# hdb44_passthrough.net
KiCad netlist of a schematic drawn in Altium Designer
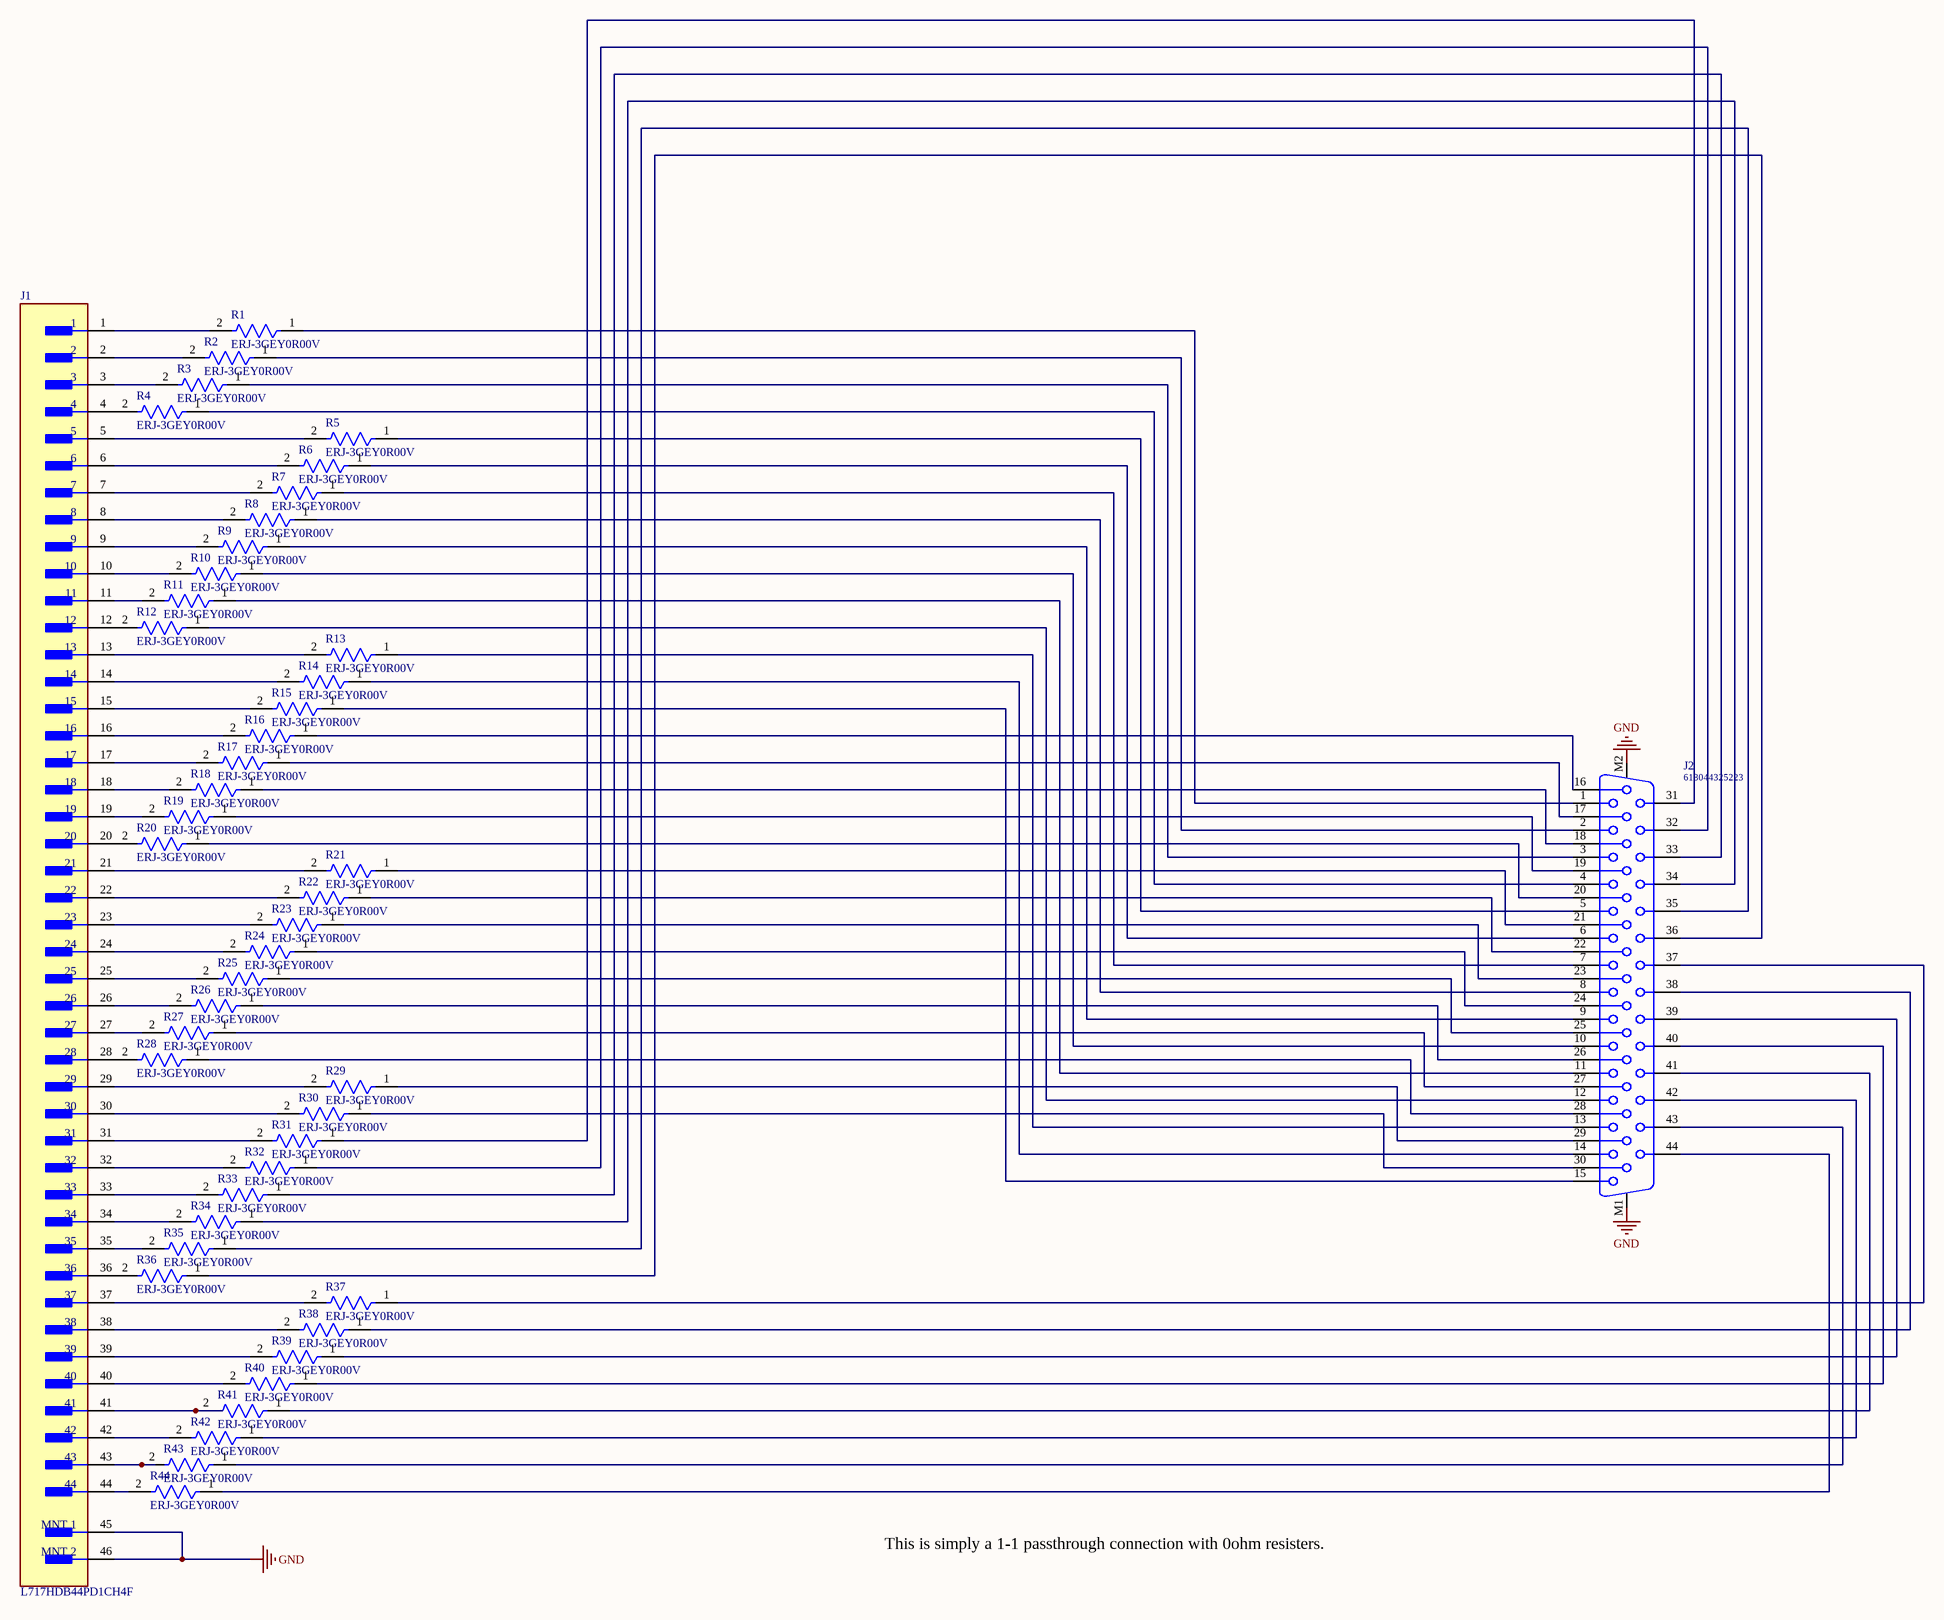
[diagram p0: hdb44_passthrough.SchDoc]

(export (version "E")
  (design (tool "Eeschema 10.0.6"))
  (components
    (comp (ref "J1")
      (value "L717HDB44PD1CH4F")
      (footprint "FP-L717HDB44PD1CH4F-MFG")
      (description "CONN DSUB HD PLUG 44POS R/A SLDR")
      (libsource (lib "Altium Content Vault") (part "41ccbbee039f7fbc4919d80e2a23f43"))
    )
    (comp (ref "J2")
      (value "618044325223")
      (footprint "618044325223")
      (description "Female High Density PCB Connector without Hex Screw WR-DSUB, Angled, 44 pins")
      (fields (field (name "MANUFACTURER") "Wurth Elektronik") (field (name "PUBLISHER") "WurthElektronik"))
      (libsource (lib "Altium Content Vault") (part "WE-CN-3S-2F-D44"))
    )
    (comp (ref "R1")
      (value "ERJ-3GEY0R00V")
      (footprint "FP-ERJ-3GEY0R00V-MFG")
      (description "RES SMD 0 OHM JUMPER 1/10W 0603")
      (fields (field (name "TOLERANCE") "5%") (field (name "MANUFACTURER") "Panasonic"))
      (libsource (lib "Altium Content Vault") (part "1029c3af85768c4190bb7ad29bc67b5"))
    )
    (comp (ref "R2")
      (value "ERJ-3GEY0R00V")
      (footprint "FP-ERJ-3GEY0R00V-MFG")
      (description "RES SMD 0 OHM JUMPER 1/10W 0603")
      (fields (field (name "TOLERANCE") "5%") (field (name "MANUFACTURER") "Panasonic"))
      (libsource (lib "Altium Content Vault") (part "1029c3af85768c4190bb7ad29bc67b5"))
    )
    (comp (ref "R3")
      (value "ERJ-3GEY0R00V")
      (footprint "FP-ERJ-3GEY0R00V-MFG")
      (description "RES SMD 0 OHM JUMPER 1/10W 0603")
      (fields (field (name "TOLERANCE") "5%") (field (name "MANUFACTURER") "Panasonic"))
      (libsource (lib "Altium Content Vault") (part "1029c3af85768c4190bb7ad29bc67b5"))
    )
    (comp (ref "R4")
      (value "ERJ-3GEY0R00V")
      (footprint "FP-ERJ-3GEY0R00V-MFG")
      (description "RES SMD 0 OHM JUMPER 1/10W 0603")
      (fields (field (name "TOLERANCE") "5%") (field (name "MANUFACTURER") "Panasonic"))
      (libsource (lib "Altium Content Vault") (part "1029c3af85768c4190bb7ad29bc67b5"))
    )
    (comp (ref "R5")
      (value "ERJ-3GEY0R00V")
      (footprint "FP-ERJ-3GEY0R00V-MFG")
      (description "RES SMD 0 OHM JUMPER 1/10W 0603")
      (fields (field (name "TOLERANCE") "5%") (field (name "MANUFACTURER") "Panasonic"))
      (libsource (lib "Altium Content Vault") (part "1029c3af85768c4190bb7ad29bc67b5"))
    )
    (comp (ref "R6")
      (value "ERJ-3GEY0R00V")
      (footprint "FP-ERJ-3GEY0R00V-MFG")
      (description "RES SMD 0 OHM JUMPER 1/10W 0603")
      (fields (field (name "TOLERANCE") "5%") (field (name "MANUFACTURER") "Panasonic"))
      (libsource (lib "Altium Content Vault") (part "1029c3af85768c4190bb7ad29bc67b5"))
    )
    (comp (ref "R7")
      (value "ERJ-3GEY0R00V")
      (footprint "FP-ERJ-3GEY0R00V-MFG")
      (description "RES SMD 0 OHM JUMPER 1/10W 0603")
      (fields (field (name "TOLERANCE") "5%") (field (name "MANUFACTURER") "Panasonic"))
      (libsource (lib "Altium Content Vault") (part "1029c3af85768c4190bb7ad29bc67b5"))
    )
    (comp (ref "R8")
      (value "ERJ-3GEY0R00V")
      (footprint "FP-ERJ-3GEY0R00V-MFG")
      (description "RES SMD 0 OHM JUMPER 1/10W 0603")
      (fields (field (name "TOLERANCE") "5%") (field (name "MANUFACTURER") "Panasonic"))
      (libsource (lib "Altium Content Vault") (part "1029c3af85768c4190bb7ad29bc67b5"))
    )
    (comp (ref "R9")
      (value "ERJ-3GEY0R00V")
      (footprint "FP-ERJ-3GEY0R00V-MFG")
      (description "RES SMD 0 OHM JUMPER 1/10W 0603")
      (fields (field (name "TOLERANCE") "5%") (field (name "MANUFACTURER") "Panasonic"))
      (libsource (lib "Altium Content Vault") (part "1029c3af85768c4190bb7ad29bc67b5"))
    )
    (comp (ref "R10")
      (value "ERJ-3GEY0R00V")
      (footprint "FP-ERJ-3GEY0R00V-MFG")
      (description "RES SMD 0 OHM JUMPER 1/10W 0603")
      (fields (field (name "TOLERANCE") "5%") (field (name "MANUFACTURER") "Panasonic"))
      (libsource (lib "Altium Content Vault") (part "1029c3af85768c4190bb7ad29bc67b5"))
    )
    (comp (ref "R11")
      (value "ERJ-3GEY0R00V")
      (footprint "FP-ERJ-3GEY0R00V-MFG")
      (description "RES SMD 0 OHM JUMPER 1/10W 0603")
      (fields (field (name "TOLERANCE") "5%") (field (name "MANUFACTURER") "Panasonic"))
      (libsource (lib "Altium Content Vault") (part "1029c3af85768c4190bb7ad29bc67b5"))
    )
    (comp (ref "R12")
      (value "ERJ-3GEY0R00V")
      (footprint "FP-ERJ-3GEY0R00V-MFG")
      (description "RES SMD 0 OHM JUMPER 1/10W 0603")
      (fields (field (name "TOLERANCE") "5%") (field (name "MANUFACTURER") "Panasonic"))
      (libsource (lib "Altium Content Vault") (part "1029c3af85768c4190bb7ad29bc67b5"))
    )
    (comp (ref "R13")
      (value "ERJ-3GEY0R00V")
      (footprint "FP-ERJ-3GEY0R00V-MFG")
      (description "RES SMD 0 OHM JUMPER 1/10W 0603")
      (fields (field (name "TOLERANCE") "5%") (field (name "MANUFACTURER") "Panasonic"))
      (libsource (lib "Altium Content Vault") (part "1029c3af85768c4190bb7ad29bc67b5"))
    )
    (comp (ref "R14")
      (value "ERJ-3GEY0R00V")
      (footprint "FP-ERJ-3GEY0R00V-MFG")
      (description "RES SMD 0 OHM JUMPER 1/10W 0603")
      (fields (field (name "TOLERANCE") "5%") (field (name "MANUFACTURER") "Panasonic"))
      (libsource (lib "Altium Content Vault") (part "1029c3af85768c4190bb7ad29bc67b5"))
    )
    (comp (ref "R15")
      (value "ERJ-3GEY0R00V")
      (footprint "FP-ERJ-3GEY0R00V-MFG")
      (description "RES SMD 0 OHM JUMPER 1/10W 0603")
      (fields (field (name "TOLERANCE") "5%") (field (name "MANUFACTURER") "Panasonic"))
      (libsource (lib "Altium Content Vault") (part "1029c3af85768c4190bb7ad29bc67b5"))
    )
    (comp (ref "R16")
      (value "ERJ-3GEY0R00V")
      (footprint "FP-ERJ-3GEY0R00V-MFG")
      (description "RES SMD 0 OHM JUMPER 1/10W 0603")
      (fields (field (name "TOLERANCE") "5%") (field (name "MANUFACTURER") "Panasonic"))
      (libsource (lib "Altium Content Vault") (part "1029c3af85768c4190bb7ad29bc67b5"))
    )
    (comp (ref "R17")
      (value "ERJ-3GEY0R00V")
      (footprint "FP-ERJ-3GEY0R00V-MFG")
      (description "RES SMD 0 OHM JUMPER 1/10W 0603")
      (fields (field (name "TOLERANCE") "5%") (field (name "MANUFACTURER") "Panasonic"))
      (libsource (lib "Altium Content Vault") (part "1029c3af85768c4190bb7ad29bc67b5"))
    )
    (comp (ref "R18")
      (value "ERJ-3GEY0R00V")
      (footprint "FP-ERJ-3GEY0R00V-MFG")
      (description "RES SMD 0 OHM JUMPER 1/10W 0603")
      (fields (field (name "TOLERANCE") "5%") (field (name "MANUFACTURER") "Panasonic"))
      (libsource (lib "Altium Content Vault") (part "1029c3af85768c4190bb7ad29bc67b5"))
    )
    (comp (ref "R19")
      (value "ERJ-3GEY0R00V")
      (footprint "FP-ERJ-3GEY0R00V-MFG")
      (description "RES SMD 0 OHM JUMPER 1/10W 0603")
      (fields (field (name "TOLERANCE") "5%") (field (name "MANUFACTURER") "Panasonic"))
      (libsource (lib "Altium Content Vault") (part "1029c3af85768c4190bb7ad29bc67b5"))
    )
    (comp (ref "R20")
      (value "ERJ-3GEY0R00V")
      (footprint "FP-ERJ-3GEY0R00V-MFG")
      (description "RES SMD 0 OHM JUMPER 1/10W 0603")
      (fields (field (name "TOLERANCE") "5%") (field (name "MANUFACTURER") "Panasonic"))
      (libsource (lib "Altium Content Vault") (part "1029c3af85768c4190bb7ad29bc67b5"))
    )
    (comp (ref "R21")
      (value "ERJ-3GEY0R00V")
      (footprint "FP-ERJ-3GEY0R00V-MFG")
      (description "RES SMD 0 OHM JUMPER 1/10W 0603")
      (fields (field (name "TOLERANCE") "5%") (field (name "MANUFACTURER") "Panasonic"))
      (libsource (lib "Altium Content Vault") (part "1029c3af85768c4190bb7ad29bc67b5"))
    )
    (comp (ref "R22")
      (value "ERJ-3GEY0R00V")
      (footprint "FP-ERJ-3GEY0R00V-MFG")
      (description "RES SMD 0 OHM JUMPER 1/10W 0603")
      (fields (field (name "TOLERANCE") "5%") (field (name "MANUFACTURER") "Panasonic"))
      (libsource (lib "Altium Content Vault") (part "1029c3af85768c4190bb7ad29bc67b5"))
    )
    (comp (ref "R23")
      (value "ERJ-3GEY0R00V")
      (footprint "FP-ERJ-3GEY0R00V-MFG")
      (description "RES SMD 0 OHM JUMPER 1/10W 0603")
      (fields (field (name "TOLERANCE") "5%") (field (name "MANUFACTURER") "Panasonic"))
      (libsource (lib "Altium Content Vault") (part "1029c3af85768c4190bb7ad29bc67b5"))
    )
    (comp (ref "R24")
      (value "ERJ-3GEY0R00V")
      (footprint "FP-ERJ-3GEY0R00V-MFG")
      (description "RES SMD 0 OHM JUMPER 1/10W 0603")
      (fields (field (name "TOLERANCE") "5%") (field (name "MANUFACTURER") "Panasonic"))
      (libsource (lib "Altium Content Vault") (part "1029c3af85768c4190bb7ad29bc67b5"))
    )
    (comp (ref "R25")
      (value "ERJ-3GEY0R00V")
      (footprint "FP-ERJ-3GEY0R00V-MFG")
      (description "RES SMD 0 OHM JUMPER 1/10W 0603")
      (fields (field (name "TOLERANCE") "5%") (field (name "MANUFACTURER") "Panasonic"))
      (libsource (lib "Altium Content Vault") (part "1029c3af85768c4190bb7ad29bc67b5"))
    )
    (comp (ref "R26")
      (value "ERJ-3GEY0R00V")
      (footprint "FP-ERJ-3GEY0R00V-MFG")
      (description "RES SMD 0 OHM JUMPER 1/10W 0603")
      (fields (field (name "TOLERANCE") "5%") (field (name "MANUFACTURER") "Panasonic"))
      (libsource (lib "Altium Content Vault") (part "1029c3af85768c4190bb7ad29bc67b5"))
    )
    (comp (ref "R27")
      (value "ERJ-3GEY0R00V")
      (footprint "FP-ERJ-3GEY0R00V-MFG")
      (description "RES SMD 0 OHM JUMPER 1/10W 0603")
      (fields (field (name "TOLERANCE") "5%") (field (name "MANUFACTURER") "Panasonic"))
      (libsource (lib "Altium Content Vault") (part "1029c3af85768c4190bb7ad29bc67b5"))
    )
    (comp (ref "R28")
      (value "ERJ-3GEY0R00V")
      (footprint "FP-ERJ-3GEY0R00V-MFG")
      (description "RES SMD 0 OHM JUMPER 1/10W 0603")
      (fields (field (name "TOLERANCE") "5%") (field (name "MANUFACTURER") "Panasonic"))
      (libsource (lib "Altium Content Vault") (part "1029c3af85768c4190bb7ad29bc67b5"))
    )
    (comp (ref "R29")
      (value "ERJ-3GEY0R00V")
      (footprint "FP-ERJ-3GEY0R00V-MFG")
      (description "RES SMD 0 OHM JUMPER 1/10W 0603")
      (fields (field (name "TOLERANCE") "5%") (field (name "MANUFACTURER") "Panasonic"))
      (libsource (lib "Altium Content Vault") (part "1029c3af85768c4190bb7ad29bc67b5"))
    )
    (comp (ref "R30")
      (value "ERJ-3GEY0R00V")
      (footprint "FP-ERJ-3GEY0R00V-MFG")
      (description "RES SMD 0 OHM JUMPER 1/10W 0603")
      (fields (field (name "TOLERANCE") "5%") (field (name "MANUFACTURER") "Panasonic"))
      (libsource (lib "Altium Content Vault") (part "1029c3af85768c4190bb7ad29bc67b5"))
    )
    (comp (ref "R31")
      (value "ERJ-3GEY0R00V")
      (footprint "FP-ERJ-3GEY0R00V-MFG")
      (description "RES SMD 0 OHM JUMPER 1/10W 0603")
      (fields (field (name "TOLERANCE") "5%") (field (name "MANUFACTURER") "Panasonic"))
      (libsource (lib "Altium Content Vault") (part "1029c3af85768c4190bb7ad29bc67b5"))
    )
    (comp (ref "R32")
      (value "ERJ-3GEY0R00V")
      (footprint "FP-ERJ-3GEY0R00V-MFG")
      (description "RES SMD 0 OHM JUMPER 1/10W 0603")
      (fields (field (name "TOLERANCE") "5%") (field (name "MANUFACTURER") "Panasonic"))
      (libsource (lib "Altium Content Vault") (part "1029c3af85768c4190bb7ad29bc67b5"))
    )
    (comp (ref "R33")
      (value "ERJ-3GEY0R00V")
      (footprint "FP-ERJ-3GEY0R00V-MFG")
      (description "RES SMD 0 OHM JUMPER 1/10W 0603")
      (fields (field (name "TOLERANCE") "5%") (field (name "MANUFACTURER") "Panasonic"))
      (libsource (lib "Altium Content Vault") (part "1029c3af85768c4190bb7ad29bc67b5"))
    )
    (comp (ref "R34")
      (value "ERJ-3GEY0R00V")
      (footprint "FP-ERJ-3GEY0R00V-MFG")
      (description "RES SMD 0 OHM JUMPER 1/10W 0603")
      (fields (field (name "TOLERANCE") "5%") (field (name "MANUFACTURER") "Panasonic"))
      (libsource (lib "Altium Content Vault") (part "1029c3af85768c4190bb7ad29bc67b5"))
    )
    (comp (ref "R35")
      (value "ERJ-3GEY0R00V")
      (footprint "FP-ERJ-3GEY0R00V-MFG")
      (description "RES SMD 0 OHM JUMPER 1/10W 0603")
      (fields (field (name "TOLERANCE") "5%") (field (name "MANUFACTURER") "Panasonic"))
      (libsource (lib "Altium Content Vault") (part "1029c3af85768c4190bb7ad29bc67b5"))
    )
    (comp (ref "R36")
      (value "ERJ-3GEY0R00V")
      (footprint "FP-ERJ-3GEY0R00V-MFG")
      (description "RES SMD 0 OHM JUMPER 1/10W 0603")
      (fields (field (name "TOLERANCE") "5%") (field (name "MANUFACTURER") "Panasonic"))
      (libsource (lib "Altium Content Vault") (part "1029c3af85768c4190bb7ad29bc67b5"))
    )
    (comp (ref "R37")
      (value "ERJ-3GEY0R00V")
      (footprint "FP-ERJ-3GEY0R00V-MFG")
      (description "RES SMD 0 OHM JUMPER 1/10W 0603")
      (fields (field (name "TOLERANCE") "5%") (field (name "MANUFACTURER") "Panasonic"))
      (libsource (lib "Altium Content Vault") (part "1029c3af85768c4190bb7ad29bc67b5"))
    )
    (comp (ref "R38")
      (value "ERJ-3GEY0R00V")
      (footprint "FP-ERJ-3GEY0R00V-MFG")
      (description "RES SMD 0 OHM JUMPER 1/10W 0603")
      (fields (field (name "TOLERANCE") "5%") (field (name "MANUFACTURER") "Panasonic"))
      (libsource (lib "Altium Content Vault") (part "1029c3af85768c4190bb7ad29bc67b5"))
    )
    (comp (ref "R39")
      (value "ERJ-3GEY0R00V")
      (footprint "FP-ERJ-3GEY0R00V-MFG")
      (description "RES SMD 0 OHM JUMPER 1/10W 0603")
      (fields (field (name "TOLERANCE") "5%") (field (name "MANUFACTURER") "Panasonic"))
      (libsource (lib "Altium Content Vault") (part "1029c3af85768c4190bb7ad29bc67b5"))
    )
    (comp (ref "R40")
      (value "ERJ-3GEY0R00V")
      (footprint "FP-ERJ-3GEY0R00V-MFG")
      (description "RES SMD 0 OHM JUMPER 1/10W 0603")
      (fields (field (name "TOLERANCE") "5%") (field (name "MANUFACTURER") "Panasonic"))
      (libsource (lib "Altium Content Vault") (part "1029c3af85768c4190bb7ad29bc67b5"))
    )
    (comp (ref "R41")
      (value "ERJ-3GEY0R00V")
      (footprint "FP-ERJ-3GEY0R00V-MFG")
      (description "RES SMD 0 OHM JUMPER 1/10W 0603")
      (fields (field (name "TOLERANCE") "5%") (field (name "MANUFACTURER") "Panasonic"))
      (libsource (lib "Altium Content Vault") (part "1029c3af85768c4190bb7ad29bc67b5"))
    )
    (comp (ref "R42")
      (value "ERJ-3GEY0R00V")
      (footprint "FP-ERJ-3GEY0R00V-MFG")
      (description "RES SMD 0 OHM JUMPER 1/10W 0603")
      (fields (field (name "TOLERANCE") "5%") (field (name "MANUFACTURER") "Panasonic"))
      (libsource (lib "Altium Content Vault") (part "1029c3af85768c4190bb7ad29bc67b5"))
    )
    (comp (ref "R43")
      (value "ERJ-3GEY0R00V")
      (footprint "FP-ERJ-3GEY0R00V-MFG")
      (description "RES SMD 0 OHM JUMPER 1/10W 0603")
      (fields (field (name "TOLERANCE") "5%") (field (name "MANUFACTURER") "Panasonic"))
      (libsource (lib "Altium Content Vault") (part "1029c3af85768c4190bb7ad29bc67b5"))
    )
    (comp (ref "R44")
      (value "ERJ-3GEY0R00V")
      (footprint "FP-ERJ-3GEY0R00V-MFG")
      (description "RES SMD 0 OHM JUMPER 1/10W 0603")
      (fields (field (name "TOLERANCE") "5%") (field (name "MANUFACTURER") "Panasonic"))
      (libsource (lib "Altium Content Vault") (part "1029c3af85768c4190bb7ad29bc67b5"))
    )
  )
  (nets
    (net (code "1") (name "GND") (class "Default")
      (node (ref "J1") (pin "45") (pinfunction "MNT_1_45") (pintype "passive"))
      (node (ref "J1") (pin "46") (pinfunction "MNT_2_46") (pintype "passive"))
      (node (ref "J2") (pin "M1") (pinfunction "M1_M1") (pintype "passive"))
      (node (ref "J2") (pin "M2") (pinfunction "M2_M2") (pintype "passive"))
    )
    (net (code "2") (name "Net-(J1-Pad1)") (class "Default")
      (node (ref "J1") (pin "1") (pinfunction "1_1") (pintype "passive"))
      (node (ref "R1") (pin "2") (pinfunction "2_2") (pintype "passive"))
    )
    (net (code "3") (name "Net-(J1-Pad2)") (class "Default")
      (node (ref "J1") (pin "2") (pinfunction "2_2") (pintype "passive"))
      (node (ref "R2") (pin "2") (pinfunction "2_2") (pintype "passive"))
    )
    (net (code "4") (name "Net-(J1-Pad3)") (class "Default")
      (node (ref "J1") (pin "3") (pinfunction "3_3") (pintype "passive"))
      (node (ref "R3") (pin "2") (pinfunction "2_2") (pintype "passive"))
    )
    (net (code "5") (name "Net-(J1-Pad4)") (class "Default")
      (node (ref "J1") (pin "4") (pinfunction "4_4") (pintype "passive"))
      (node (ref "R4") (pin "2") (pinfunction "2_2") (pintype "passive"))
    )
    (net (code "6") (name "Net-(J1-Pad5)") (class "Default")
      (node (ref "J1") (pin "5") (pinfunction "5_5") (pintype "passive"))
      (node (ref "R5") (pin "2") (pinfunction "2_2") (pintype "passive"))
    )
    (net (code "7") (name "Net-(J1-Pad6)") (class "Default")
      (node (ref "J1") (pin "6") (pinfunction "6_6") (pintype "passive"))
      (node (ref "R6") (pin "2") (pinfunction "2_2") (pintype "passive"))
    )
    (net (code "8") (name "Net-(J1-Pad7)") (class "Default")
      (node (ref "J1") (pin "7") (pinfunction "7_7") (pintype "passive"))
      (node (ref "R7") (pin "2") (pinfunction "2_2") (pintype "passive"))
    )
    (net (code "9") (name "Net-(J1-Pad8)") (class "Default")
      (node (ref "J1") (pin "8") (pinfunction "8_8") (pintype "passive"))
      (node (ref "R8") (pin "2") (pinfunction "2_2") (pintype "passive"))
    )
    (net (code "10") (name "Net-(J1-Pad9)") (class "Default")
      (node (ref "J1") (pin "9") (pinfunction "9_9") (pintype "passive"))
      (node (ref "R9") (pin "2") (pinfunction "2_2") (pintype "passive"))
    )
    (net (code "11") (name "Net-(J1-Pad10)") (class "Default")
      (node (ref "J1") (pin "10") (pinfunction "10_10") (pintype "passive"))
      (node (ref "R10") (pin "2") (pinfunction "2_2") (pintype "passive"))
    )
    (net (code "12") (name "Net-(J1-Pad11)") (class "Default")
      (node (ref "J1") (pin "11") (pinfunction "11_11") (pintype "passive"))
      (node (ref "R11") (pin "2") (pinfunction "2_2") (pintype "passive"))
    )
    (net (code "13") (name "Net-(J1-Pad12)") (class "Default")
      (node (ref "J1") (pin "12") (pinfunction "12_12") (pintype "passive"))
      (node (ref "R12") (pin "2") (pinfunction "2_2") (pintype "passive"))
    )
    (net (code "14") (name "Net-(J1-Pad13)") (class "Default")
      (node (ref "J1") (pin "13") (pinfunction "13_13") (pintype "passive"))
      (node (ref "R13") (pin "2") (pinfunction "2_2") (pintype "passive"))
    )
    (net (code "15") (name "Net-(J1-Pad14)") (class "Default")
      (node (ref "J1") (pin "14") (pinfunction "14_14") (pintype "passive"))
      (node (ref "R14") (pin "2") (pinfunction "2_2") (pintype "passive"))
    )
    (net (code "16") (name "Net-(J1-Pad15)") (class "Default")
      (node (ref "J1") (pin "15") (pinfunction "15_15") (pintype "passive"))
      (node (ref "R15") (pin "2") (pinfunction "2_2") (pintype "passive"))
    )
    (net (code "17") (name "Net-(J1-Pad16)") (class "Default")
      (node (ref "J1") (pin "16") (pinfunction "16_16") (pintype "passive"))
      (node (ref "R16") (pin "2") (pinfunction "2_2") (pintype "passive"))
    )
    (net (code "18") (name "Net-(J1-Pad17)") (class "Default")
      (node (ref "J1") (pin "17") (pinfunction "17_17") (pintype "passive"))
      (node (ref "R17") (pin "2") (pinfunction "2_2") (pintype "passive"))
    )
    (net (code "19") (name "Net-(J1-Pad18)") (class "Default")
      (node (ref "J1") (pin "18") (pinfunction "18_18") (pintype "passive"))
      (node (ref "R18") (pin "2") (pinfunction "2_2") (pintype "passive"))
    )
    (net (code "20") (name "Net-(J1-Pad19)") (class "Default")
      (node (ref "J1") (pin "19") (pinfunction "19_19") (pintype "passive"))
      (node (ref "R19") (pin "2") (pinfunction "2_2") (pintype "passive"))
    )
    (net (code "21") (name "Net-(J1-Pad20)") (class "Default")
      (node (ref "J1") (pin "20") (pinfunction "20_20") (pintype "passive"))
      (node (ref "R20") (pin "2") (pinfunction "2_2") (pintype "passive"))
    )
    (net (code "22") (name "Net-(J1-Pad21)") (class "Default")
      (node (ref "J1") (pin "21") (pinfunction "21_21") (pintype "passive"))
      (node (ref "R21") (pin "2") (pinfunction "2_2") (pintype "passive"))
    )
    (net (code "23") (name "Net-(J1-Pad22)") (class "Default")
      (node (ref "J1") (pin "22") (pinfunction "22_22") (pintype "passive"))
      (node (ref "R22") (pin "2") (pinfunction "2_2") (pintype "passive"))
    )
    (net (code "24") (name "Net-(J1-Pad23)") (class "Default")
      (node (ref "J1") (pin "23") (pinfunction "23_23") (pintype "passive"))
      (node (ref "R23") (pin "2") (pinfunction "2_2") (pintype "passive"))
    )
    (net (code "25") (name "Net-(J1-Pad24)") (class "Default")
      (node (ref "J1") (pin "24") (pinfunction "24_24") (pintype "passive"))
      (node (ref "R24") (pin "2") (pinfunction "2_2") (pintype "passive"))
    )
    (net (code "26") (name "Net-(J1-Pad25)") (class "Default")
      (node (ref "J1") (pin "25") (pinfunction "25_25") (pintype "passive"))
      (node (ref "R25") (pin "2") (pinfunction "2_2") (pintype "passive"))
    )
    (net (code "27") (name "Net-(J1-Pad26)") (class "Default")
      (node (ref "J1") (pin "26") (pinfunction "26_26") (pintype "passive"))
      (node (ref "R26") (pin "2") (pinfunction "2_2") (pintype "passive"))
    )
    (net (code "28") (name "Net-(J1-Pad27)") (class "Default")
      (node (ref "J1") (pin "27") (pinfunction "27_27") (pintype "passive"))
      (node (ref "R27") (pin "2") (pinfunction "2_2") (pintype "passive"))
    )
    (net (code "29") (name "Net-(J1-Pad28)") (class "Default")
      (node (ref "J1") (pin "28") (pinfunction "28_28") (pintype "passive"))
      (node (ref "R28") (pin "2") (pinfunction "2_2") (pintype "passive"))
    )
    (net (code "30") (name "Net-(J1-Pad29)") (class "Default")
      (node (ref "J1") (pin "29") (pinfunction "29_29") (pintype "passive"))
      (node (ref "R29") (pin "2") (pinfunction "2_2") (pintype "passive"))
    )
    (net (code "31") (name "Net-(J1-Pad30)") (class "Default")
      (node (ref "J1") (pin "30") (pinfunction "30_30") (pintype "passive"))
      (node (ref "R30") (pin "2") (pinfunction "2_2") (pintype "passive"))
    )
    (net (code "32") (name "Net-(J1-Pad31)") (class "Default")
      (node (ref "J1") (pin "31") (pinfunction "31_31") (pintype "passive"))
      (node (ref "R31") (pin "2") (pinfunction "2_2") (pintype "passive"))
    )
    (net (code "33") (name "Net-(J1-Pad32)") (class "Default")
      (node (ref "J1") (pin "32") (pinfunction "32_32") (pintype "passive"))
      (node (ref "R32") (pin "2") (pinfunction "2_2") (pintype "passive"))
    )
    (net (code "34") (name "Net-(J1-Pad33)") (class "Default")
      (node (ref "J1") (pin "33") (pinfunction "33_33") (pintype "passive"))
      (node (ref "R33") (pin "2") (pinfunction "2_2") (pintype "passive"))
    )
    (net (code "35") (name "Net-(J1-Pad34)") (class "Default")
      (node (ref "J1") (pin "34") (pinfunction "34_34") (pintype "passive"))
      (node (ref "R34") (pin "2") (pinfunction "2_2") (pintype "passive"))
    )
    (net (code "36") (name "Net-(J1-Pad35)") (class "Default")
      (node (ref "J1") (pin "35") (pinfunction "35_35") (pintype "passive"))
      (node (ref "R35") (pin "2") (pinfunction "2_2") (pintype "passive"))
    )
    (net (code "37") (name "Net-(J1-Pad36)") (class "Default")
      (node (ref "J1") (pin "36") (pinfunction "36_36") (pintype "passive"))
      (node (ref "R36") (pin "2") (pinfunction "2_2") (pintype "passive"))
    )
    (net (code "38") (name "Net-(J1-Pad37)") (class "Default")
      (node (ref "J1") (pin "37") (pinfunction "37_37") (pintype "passive"))
      (node (ref "R37") (pin "2") (pinfunction "2_2") (pintype "passive"))
    )
    (net (code "39") (name "Net-(J1-Pad38)") (class "Default")
      (node (ref "J1") (pin "38") (pinfunction "38_38") (pintype "passive"))
      (node (ref "R38") (pin "2") (pinfunction "2_2") (pintype "passive"))
    )
    (net (code "40") (name "Net-(J1-Pad39)") (class "Default")
      (node (ref "J1") (pin "39") (pinfunction "39_39") (pintype "passive"))
      (node (ref "R39") (pin "2") (pinfunction "2_2") (pintype "passive"))
    )
    (net (code "41") (name "Net-(J1-Pad40)") (class "Default")
      (node (ref "J1") (pin "40") (pinfunction "40_40") (pintype "passive"))
      (node (ref "R40") (pin "2") (pinfunction "2_2") (pintype "passive"))
    )
    (net (code "42") (name "Net-(J1-Pad41)") (class "Default")
      (node (ref "J1") (pin "41") (pinfunction "41_41") (pintype "passive"))
      (node (ref "R41") (pin "2") (pinfunction "2_2") (pintype "passive"))
    )
    (net (code "43") (name "Net-(J1-Pad42)") (class "Default")
      (node (ref "J1") (pin "42") (pinfunction "42_42") (pintype "passive"))
      (node (ref "R42") (pin "2") (pinfunction "2_2") (pintype "passive"))
    )
    (net (code "44") (name "Net-(J1-Pad43)") (class "Default")
      (node (ref "J1") (pin "43") (pinfunction "43_43") (pintype "passive"))
      (node (ref "R43") (pin "2") (pinfunction "2_2") (pintype "passive"))
    )
    (net (code "45") (name "Net-(J1-Pad44)") (class "Default")
      (node (ref "J1") (pin "44") (pinfunction "44_44") (pintype "passive"))
      (node (ref "R44") (pin "2") (pinfunction "2_2") (pintype "passive"))
    )
    (net (code "46") (name "Net-(J2-Pad1)") (class "Default")
      (node (ref "J2") (pin "1") (pinfunction "1_1") (pintype "passive"))
      (node (ref "R1") (pin "1") (pinfunction "1_1") (pintype "passive"))
    )
    (net (code "47") (name "Net-(J2-Pad2)") (class "Default")
      (node (ref "J2") (pin "2") (pinfunction "2_2") (pintype "passive"))
      (node (ref "R2") (pin "1") (pinfunction "1_1") (pintype "passive"))
    )
    (net (code "48") (name "Net-(J2-Pad3)") (class "Default")
      (node (ref "J2") (pin "3") (pinfunction "3_3") (pintype "passive"))
      (node (ref "R3") (pin "1") (pinfunction "1_1") (pintype "passive"))
    )
    (net (code "49") (name "Net-(J2-Pad4)") (class "Default")
      (node (ref "J2") (pin "4") (pinfunction "4_4") (pintype "passive"))
      (node (ref "R4") (pin "1") (pinfunction "1_1") (pintype "passive"))
    )
    (net (code "50") (name "Net-(J2-Pad5)") (class "Default")
      (node (ref "J2") (pin "5") (pinfunction "5_5") (pintype "passive"))
      (node (ref "R5") (pin "1") (pinfunction "1_1") (pintype "passive"))
    )
    (net (code "51") (name "Net-(J2-Pad6)") (class "Default")
      (node (ref "J2") (pin "6") (pinfunction "6_6") (pintype "passive"))
      (node (ref "R6") (pin "1") (pinfunction "1_1") (pintype "passive"))
    )
    (net (code "52") (name "Net-(J2-Pad7)") (class "Default")
      (node (ref "J2") (pin "7") (pinfunction "7_7") (pintype "passive"))
      (node (ref "R7") (pin "1") (pinfunction "1_1") (pintype "passive"))
    )
    (net (code "53") (name "Net-(J2-Pad8)") (class "Default")
      (node (ref "J2") (pin "8") (pinfunction "8_8") (pintype "passive"))
      (node (ref "R8") (pin "1") (pinfunction "1_1") (pintype "passive"))
    )
    (net (code "54") (name "Net-(J2-Pad9)") (class "Default")
      (node (ref "J2") (pin "9") (pinfunction "9_9") (pintype "passive"))
      (node (ref "R9") (pin "1") (pinfunction "1_1") (pintype "passive"))
    )
    (net (code "55") (name "Net-(J2-Pad10)") (class "Default")
      (node (ref "J2") (pin "10") (pinfunction "10_10") (pintype "passive"))
      (node (ref "R10") (pin "1") (pinfunction "1_1") (pintype "passive"))
    )
    (net (code "56") (name "Net-(J2-Pad11)") (class "Default")
      (node (ref "J2") (pin "11") (pinfunction "11_11") (pintype "passive"))
      (node (ref "R11") (pin "1") (pinfunction "1_1") (pintype "passive"))
    )
    (net (code "57") (name "Net-(J2-Pad12)") (class "Default")
      (node (ref "J2") (pin "12") (pinfunction "12_12") (pintype "passive"))
      (node (ref "R12") (pin "1") (pinfunction "1_1") (pintype "passive"))
    )
    (net (code "58") (name "Net-(J2-Pad13)") (class "Default")
      (node (ref "J2") (pin "13") (pinfunction "13_13") (pintype "passive"))
      (node (ref "R13") (pin "1") (pinfunction "1_1") (pintype "passive"))
    )
    (net (code "59") (name "Net-(J2-Pad14)") (class "Default")
      (node (ref "J2") (pin "14") (pinfunction "14_14") (pintype "passive"))
      (node (ref "R14") (pin "1") (pinfunction "1_1") (pintype "passive"))
    )
    (net (code "60") (name "Net-(J2-Pad15)") (class "Default")
      (node (ref "J2") (pin "15") (pinfunction "15_15") (pintype "passive"))
      (node (ref "R15") (pin "1") (pinfunction "1_1") (pintype "passive"))
    )
    (net (code "61") (name "Net-(J2-Pad16)") (class "Default")
      (node (ref "J2") (pin "16") (pinfunction "16_16") (pintype "passive"))
      (node (ref "R16") (pin "1") (pinfunction "1_1") (pintype "passive"))
    )
    (net (code "62") (name "Net-(J2-Pad17)") (class "Default")
      (node (ref "J2") (pin "17") (pinfunction "17_17") (pintype "passive"))
      (node (ref "R17") (pin "1") (pinfunction "1_1") (pintype "passive"))
    )
    (net (code "63") (name "Net-(J2-Pad18)") (class "Default")
      (node (ref "J2") (pin "18") (pinfunction "18_18") (pintype "passive"))
      (node (ref "R18") (pin "1") (pinfunction "1_1") (pintype "passive"))
    )
    (net (code "64") (name "Net-(J2-Pad19)") (class "Default")
      (node (ref "J2") (pin "19") (pinfunction "19_19") (pintype "passive"))
      (node (ref "R19") (pin "1") (pinfunction "1_1") (pintype "passive"))
    )
    (net (code "65") (name "Net-(J2-Pad20)") (class "Default")
      (node (ref "J2") (pin "20") (pinfunction "20_20") (pintype "passive"))
      (node (ref "R20") (pin "1") (pinfunction "1_1") (pintype "passive"))
    )
    (net (code "66") (name "Net-(J2-Pad21)") (class "Default")
      (node (ref "J2") (pin "21") (pinfunction "21_21") (pintype "passive"))
      (node (ref "R21") (pin "1") (pinfunction "1_1") (pintype "passive"))
    )
    (net (code "67") (name "Net-(J2-Pad22)") (class "Default")
      (node (ref "J2") (pin "22") (pinfunction "22_22") (pintype "passive"))
      (node (ref "R22") (pin "1") (pinfunction "1_1") (pintype "passive"))
    )
    (net (code "68") (name "Net-(J2-Pad23)") (class "Default")
      (node (ref "J2") (pin "23") (pinfunction "23_23") (pintype "passive"))
      (node (ref "R23") (pin "1") (pinfunction "1_1") (pintype "passive"))
    )
    (net (code "69") (name "Net-(J2-Pad24)") (class "Default")
      (node (ref "J2") (pin "24") (pinfunction "24_24") (pintype "passive"))
      (node (ref "R24") (pin "1") (pinfunction "1_1") (pintype "passive"))
    )
    (net (code "70") (name "Net-(J2-Pad25)") (class "Default")
      (node (ref "J2") (pin "25") (pinfunction "25_25") (pintype "passive"))
      (node (ref "R25") (pin "1") (pinfunction "1_1") (pintype "passive"))
    )
    (net (code "71") (name "Net-(J2-Pad26)") (class "Default")
      (node (ref "J2") (pin "26") (pinfunction "26_26") (pintype "passive"))
      (node (ref "R26") (pin "1") (pinfunction "1_1") (pintype "passive"))
    )
    (net (code "72") (name "Net-(J2-Pad27)") (class "Default")
      (node (ref "J2") (pin "27") (pinfunction "27_27") (pintype "passive"))
      (node (ref "R27") (pin "1") (pinfunction "1_1") (pintype "passive"))
    )
    (net (code "73") (name "Net-(J2-Pad28)") (class "Default")
      (node (ref "J2") (pin "28") (pinfunction "28_28") (pintype "passive"))
      (node (ref "R28") (pin "1") (pinfunction "1_1") (pintype "passive"))
    )
    (net (code "74") (name "Net-(J2-Pad29)") (class "Default")
      (node (ref "J2") (pin "29") (pinfunction "29_29") (pintype "passive"))
      (node (ref "R29") (pin "1") (pinfunction "1_1") (pintype "passive"))
    )
    (net (code "75") (name "Net-(J2-Pad30)") (class "Default")
      (node (ref "J2") (pin "30") (pinfunction "30_30") (pintype "passive"))
      (node (ref "R30") (pin "1") (pinfunction "1_1") (pintype "passive"))
    )
    (net (code "76") (name "Net-(J2-Pad31)") (class "Default")
      (node (ref "J2") (pin "31") (pinfunction "31_31") (pintype "passive"))
      (node (ref "R31") (pin "1") (pinfunction "1_1") (pintype "passive"))
    )
    (net (code "77") (name "Net-(J2-Pad32)") (class "Default")
      (node (ref "J2") (pin "32") (pinfunction "32_32") (pintype "passive"))
      (node (ref "R32") (pin "1") (pinfunction "1_1") (pintype "passive"))
    )
    (net (code "78") (name "Net-(J2-Pad33)") (class "Default")
      (node (ref "J2") (pin "33") (pinfunction "33_33") (pintype "passive"))
      (node (ref "R33") (pin "1") (pinfunction "1_1") (pintype "passive"))
    )
    (net (code "79") (name "Net-(J2-Pad34)") (class "Default")
      (node (ref "J2") (pin "34") (pinfunction "34_34") (pintype "passive"))
      (node (ref "R34") (pin "1") (pinfunction "1_1") (pintype "passive"))
    )
    (net (code "80") (name "Net-(J2-Pad35)") (class "Default")
      (node (ref "J2") (pin "35") (pinfunction "35_35") (pintype "passive"))
      (node (ref "R35") (pin "1") (pinfunction "1_1") (pintype "passive"))
    )
    (net (code "81") (name "Net-(J2-Pad36)") (class "Default")
      (node (ref "J2") (pin "36") (pinfunction "36_36") (pintype "passive"))
      (node (ref "R36") (pin "1") (pinfunction "1_1") (pintype "passive"))
    )
    (net (code "82") (name "Net-(J2-Pad37)") (class "Default")
      (node (ref "J2") (pin "37") (pinfunction "37_37") (pintype "passive"))
      (node (ref "R37") (pin "1") (pinfunction "1_1") (pintype "passive"))
    )
    (net (code "83") (name "Net-(J2-Pad38)") (class "Default")
      (node (ref "J2") (pin "38") (pinfunction "38_38") (pintype "passive"))
      (node (ref "R38") (pin "1") (pinfunction "1_1") (pintype "passive"))
    )
    (net (code "84") (name "Net-(J2-Pad39)") (class "Default")
      (node (ref "J2") (pin "39") (pinfunction "39_39") (pintype "passive"))
      (node (ref "R39") (pin "1") (pinfunction "1_1") (pintype "passive"))
    )
    (net (code "85") (name "Net-(J2-Pad40)") (class "Default")
      (node (ref "J2") (pin "40") (pinfunction "40_40") (pintype "passive"))
      (node (ref "R40") (pin "1") (pinfunction "1_1") (pintype "passive"))
    )
    (net (code "86") (name "Net-(J2-Pad41)") (class "Default")
      (node (ref "J2") (pin "41") (pinfunction "41_41") (pintype "passive"))
      (node (ref "R41") (pin "1") (pinfunction "1_1") (pintype "passive"))
    )
    (net (code "87") (name "Net-(J2-Pad42)") (class "Default")
      (node (ref "J2") (pin "42") (pinfunction "42_42") (pintype "passive"))
      (node (ref "R42") (pin "1") (pinfunction "1_1") (pintype "passive"))
    )
    (net (code "88") (name "Net-(J2-Pad43)") (class "Default")
      (node (ref "J2") (pin "43") (pinfunction "43_43") (pintype "passive"))
      (node (ref "R43") (pin "1") (pinfunction "1_1") (pintype "passive"))
    )
    (net (code "89") (name "Net-(J2-Pad44)") (class "Default")
      (node (ref "J2") (pin "44") (pinfunction "44_44") (pintype "passive"))
      (node (ref "R44") (pin "1") (pinfunction "1_1") (pintype "passive"))
    )
  )
)
